# MegaShield.net
KiCad netlist of a schematic drawn in EAGLE
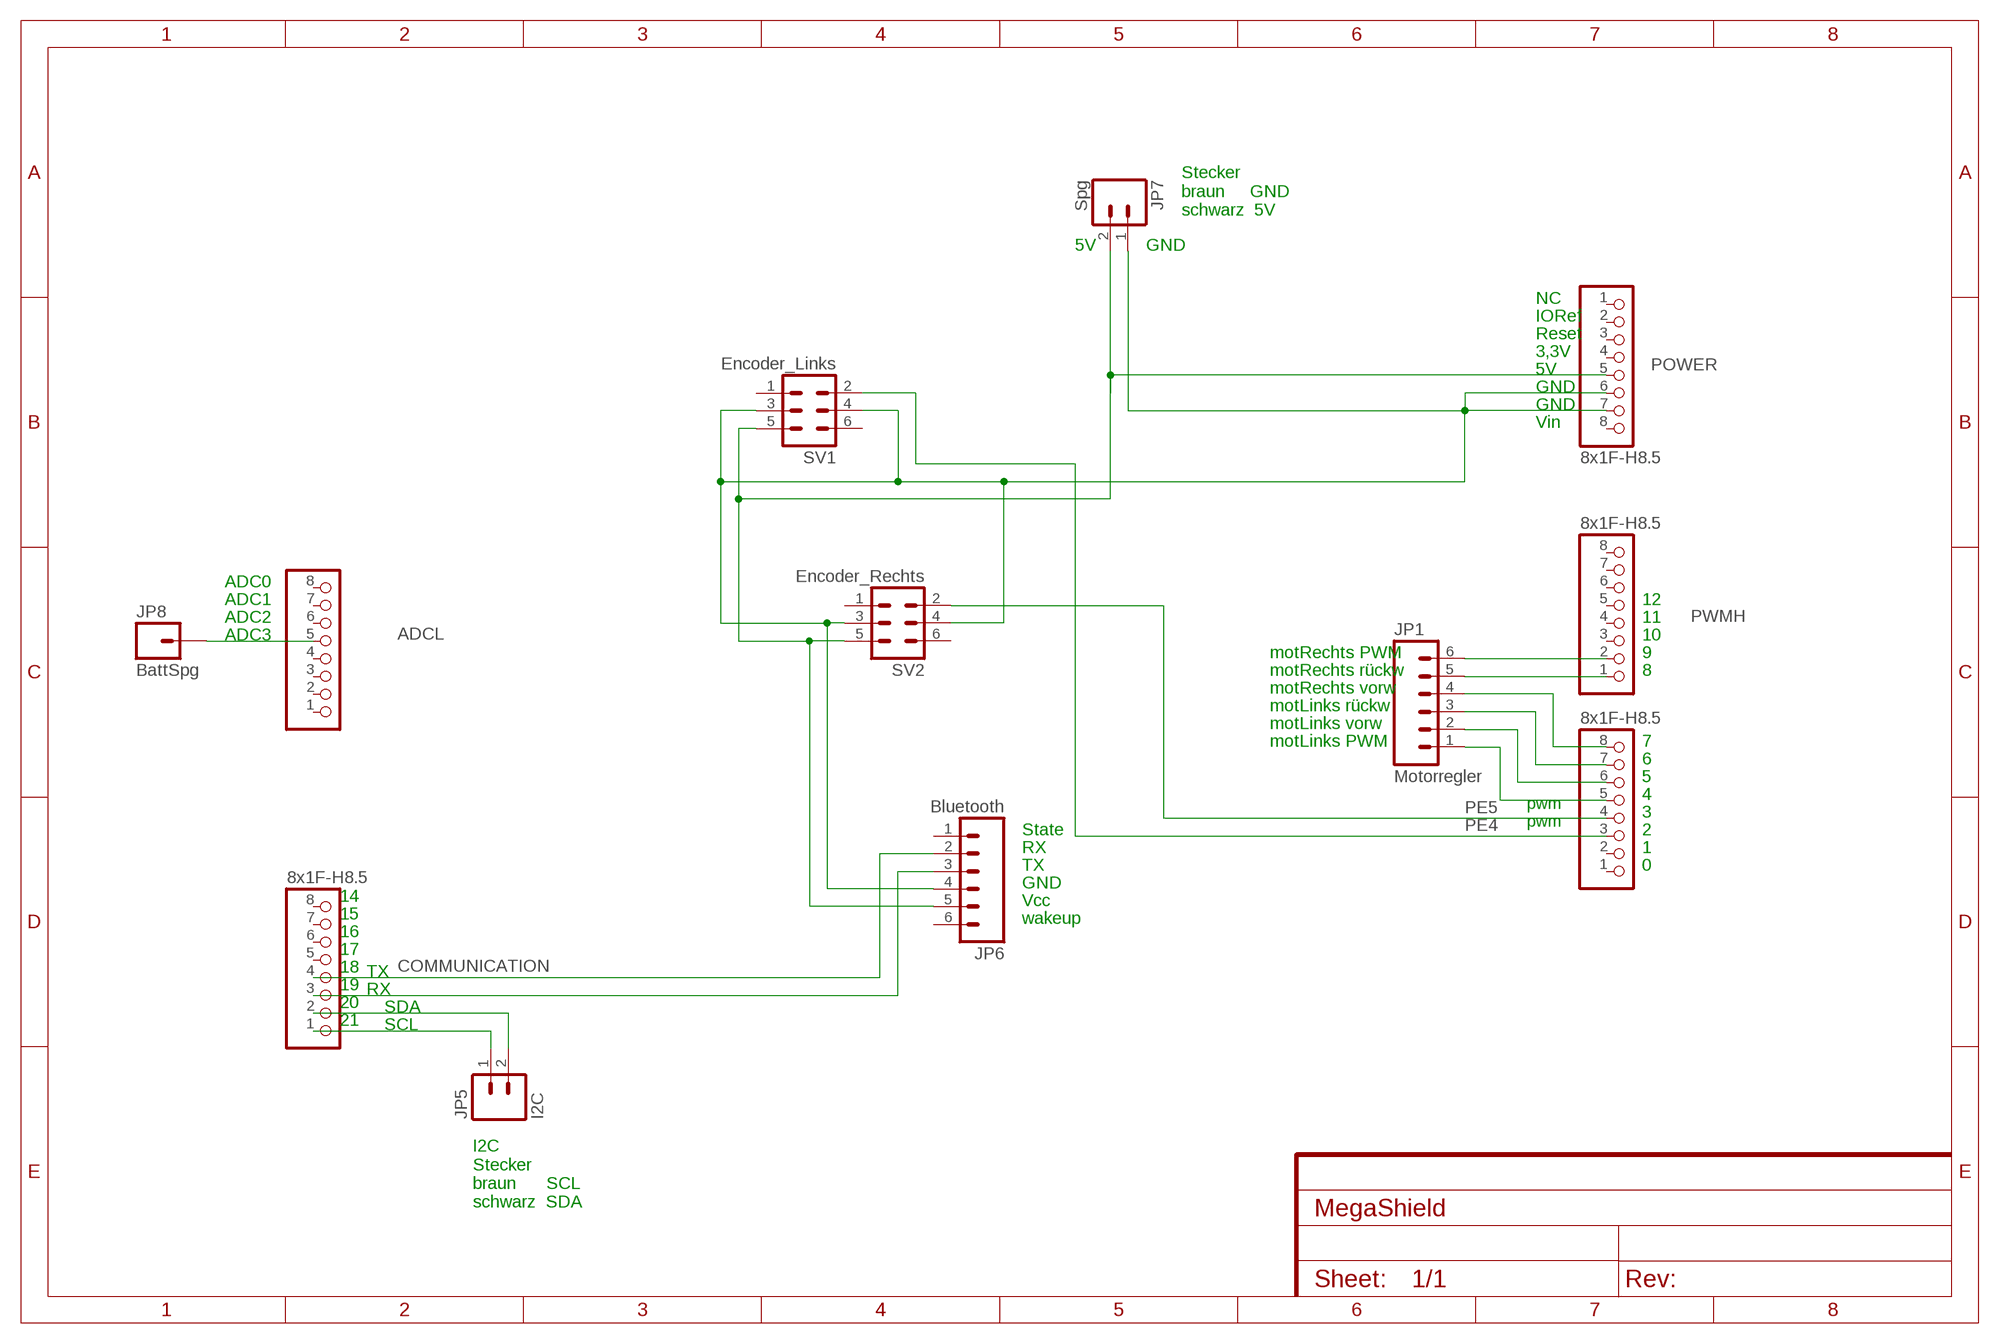
[diagram p0: schematic, sheet 1]

(export (version "E")
  (design (tool "Eeschema 10.0.6"))
  (components
    (comp (ref "ADCL")
      (value "8x1F-H8.5")
      (footprint "eagle-import:1X08")
      (libsource (lib "eagle-import") (part "PINHD-1X8"))
    )
    (comp (ref "COMMUNICATION")
      (value "8x1F-H8.5")
      (footprint "eagle-import:1X08")
      (libsource (lib "eagle-import") (part "PINHD-1X8"))
    )
    (comp (ref "JP1")
      (value "Motorregler")
      (footprint "eagle-import:1X06_LOCK")
      (libsource (lib "eagle-import") (part "M06LOCK"))
    )
    (comp (ref "JP5")
      (value "I2C")
      (footprint "eagle-import:JST-2-SMD")
      (libsource (lib "eagle-import") (part "M02-JST-2MM-SMT"))
    )
    (comp (ref "JP6")
      (value "Bluetooth")
      (footprint "eagle-import:1X06_LOCK")
      (libsource (lib "eagle-import") (part "M06LOCK"))
    )
    (comp (ref "JP7")
      (value "Spg")
      (footprint "eagle-import:JST-2-SMD")
      (libsource (lib "eagle-import") (part "M02-JST-2MM-SMT"))
    )
    (comp (ref "JP8")
      (value "BattSpg")
      (footprint "eagle-import:1X01")
      (libsource (lib "eagle-import") (part "M01PTH"))
    )
    (comp (ref "POWER")
      (value "8x1F-H8.5")
      (footprint "eagle-import:1X08")
      (libsource (lib "eagle-import") (part "PINHD-1X8"))
    )
    (comp (ref "PWMH")
      (value "8x1F-H8.5")
      (footprint "eagle-import:1X08")
      (libsource (lib "eagle-import") (part "PINHD-1X8"))
    )
    (comp (ref "PWML")
      (value "8x1F-H8.5")
      (footprint "eagle-import:1X08")
      (libsource (lib "eagle-import") (part "PINHD-1X8"))
    )
    (comp (ref "SV1")
      (value "Encoder_Links")
      (footprint "eagle-import:ML6")
      (libsource (lib "eagle-import") (part "ML6"))
    )
    (comp (ref "SV2")
      (value "Encoder_Rechts")
      (footprint "eagle-import:ML6")
      (libsource (lib "eagle-import") (part "ML6"))
    )
  )
  (nets
    (net (code "1") (name "/PE4") (class "Default")
      (node (ref "PWML") (pin "3") (pinfunction "3_3") (pintype "passive"))
      (node (ref "SV1") (pin "2") (pinfunction "2_2") (pintype "passive"))
    )
    (net (code "2") (name "/PE5") (class "Default")
      (node (ref "PWML") (pin "4") (pinfunction "4_4") (pintype "passive"))
      (node (ref "SV2") (pin "2") (pinfunction "2_2") (pintype "passive"))
    )
    (net (code "3") (name "Net-(ADCL-Pad5)") (class "Default")
      (node (ref "ADCL") (pin "5") (pinfunction "5_5") (pintype "passive"))
      (node (ref "JP8") (pin "1") (pinfunction "1_1") (pintype "passive"))
    )
    (net (code "4") (name "Net-(COMMUNICATION-Pad3)") (class "Default")
      (node (ref "COMMUNICATION") (pin "3") (pinfunction "3_3") (pintype "passive"))
      (node (ref "JP6") (pin "3") (pinfunction "3_3") (pintype "passive"))
    )
    (net (code "5") (name "Net-(COMMUNICATION-Pad4)") (class "Default")
      (node (ref "COMMUNICATION") (pin "4") (pinfunction "4_4") (pintype "passive"))
      (node (ref "JP6") (pin "2") (pinfunction "2_2") (pintype "passive"))
    )
    (net (code "6") (name "Net-(JP1-Pad1)") (class "Default")
      (node (ref "JP1") (pin "1") (pinfunction "1_1") (pintype "passive"))
      (node (ref "PWML") (pin "5") (pinfunction "5_5") (pintype "passive"))
    )
    (net (code "7") (name "Net-(JP1-Pad2)") (class "Default")
      (node (ref "JP1") (pin "2") (pinfunction "2_2") (pintype "passive"))
      (node (ref "PWML") (pin "6") (pinfunction "6_6") (pintype "passive"))
    )
    (net (code "8") (name "Net-(JP1-Pad3)") (class "Default")
      (node (ref "JP1") (pin "3") (pinfunction "3_3") (pintype "passive"))
      (node (ref "PWML") (pin "7") (pinfunction "7_7") (pintype "passive"))
    )
    (net (code "9") (name "Net-(JP1-Pad4)") (class "Default")
      (node (ref "JP1") (pin "4") (pinfunction "4_4") (pintype "passive"))
      (node (ref "PWML") (pin "8") (pinfunction "8_8") (pintype "passive"))
    )
    (net (code "10") (name "Net-(JP1-Pad5)") (class "Default")
      (node (ref "JP1") (pin "5") (pinfunction "5_5") (pintype "passive"))
      (node (ref "PWMH") (pin "1") (pinfunction "1_1") (pintype "passive"))
    )
    (net (code "11") (name "Net-(JP1-Pad6)") (class "Default")
      (node (ref "JP1") (pin "6") (pinfunction "6_6") (pintype "passive"))
      (node (ref "PWMH") (pin "2") (pinfunction "2_2") (pintype "passive"))
    )
    (net (code "12") (name "Net-(JP5-1)") (class "Default")
      (node (ref "COMMUNICATION") (pin "2") (pinfunction "2_2") (pintype "passive"))
      (node (ref "JP5") (pin "2") (pinfunction "1_2") (pintype "passive"))
    )
    (net (code "13") (name "Net-(JP5-2)") (class "Default")
      (node (ref "COMMUNICATION") (pin "1") (pinfunction "1_1") (pintype "passive"))
      (node (ref "JP5") (pin "1") (pinfunction "2_1") (pintype "passive"))
    )
    (net (code "14") (name "Net-(JP7-1)") (class "Default")
      (node (ref "JP6") (pin "5") (pinfunction "5_5") (pintype "passive"))
      (node (ref "JP7") (pin "2") (pinfunction "1_2") (pintype "passive"))
      (node (ref "POWER") (pin "5") (pinfunction "5_5") (pintype "passive"))
      (node (ref "SV1") (pin "5") (pinfunction "5_5") (pintype "passive"))
      (node (ref "SV2") (pin "5") (pinfunction "5_5") (pintype "passive"))
    )
    (net (code "15") (name "Net-(JP7-2)") (class "Default")
      (node (ref "JP6") (pin "4") (pinfunction "4_4") (pintype "passive"))
      (node (ref "JP7") (pin "1") (pinfunction "2_1") (pintype "passive"))
      (node (ref "POWER") (pin "6") (pinfunction "6_6") (pintype "passive"))
      (node (ref "POWER") (pin "7") (pinfunction "7_7") (pintype "passive"))
      (node (ref "SV1") (pin "3") (pinfunction "3_3") (pintype "passive"))
      (node (ref "SV1") (pin "4") (pinfunction "4_4") (pintype "passive"))
      (node (ref "SV2") (pin "3") (pinfunction "3_3") (pintype "passive"))
      (node (ref "SV2") (pin "4") (pinfunction "4_4") (pintype "passive"))
    )
    (net (code "16") (name "unconnected-(ADCL-Pad1)") (class "Default")
      (node (ref "ADCL") (pin "1") (pinfunction "1_1") (pintype "passive"))
    )
    (net (code "17") (name "unconnected-(ADCL-Pad2)") (class "Default")
      (node (ref "ADCL") (pin "2") (pinfunction "2_2") (pintype "passive"))
    )
    (net (code "18") (name "unconnected-(ADCL-Pad3)") (class "Default")
      (node (ref "ADCL") (pin "3") (pinfunction "3_3") (pintype "passive"))
    )
    (net (code "19") (name "unconnected-(ADCL-Pad4)") (class "Default")
      (node (ref "ADCL") (pin "4") (pinfunction "4_4") (pintype "passive"))
    )
    (net (code "20") (name "unconnected-(ADCL-Pad6)") (class "Default")
      (node (ref "ADCL") (pin "6") (pinfunction "6_6") (pintype "passive"))
    )
    (net (code "21") (name "unconnected-(ADCL-Pad7)") (class "Default")
      (node (ref "ADCL") (pin "7") (pinfunction "7_7") (pintype "passive"))
    )
    (net (code "22") (name "unconnected-(ADCL-Pad8)") (class "Default")
      (node (ref "ADCL") (pin "8") (pinfunction "8_8") (pintype "passive"))
    )
    (net (code "23") (name "unconnected-(COMMUNICATION-Pad5)") (class "Default")
      (node (ref "COMMUNICATION") (pin "5") (pinfunction "5_5") (pintype "passive"))
    )
    (net (code "24") (name "unconnected-(COMMUNICATION-Pad6)") (class "Default")
      (node (ref "COMMUNICATION") (pin "6") (pinfunction "6_6") (pintype "passive"))
    )
    (net (code "25") (name "unconnected-(COMMUNICATION-Pad7)") (class "Default")
      (node (ref "COMMUNICATION") (pin "7") (pinfunction "7_7") (pintype "passive"))
    )
    (net (code "26") (name "unconnected-(COMMUNICATION-Pad8)") (class "Default")
      (node (ref "COMMUNICATION") (pin "8") (pinfunction "8_8") (pintype "passive"))
    )
    (net (code "27") (name "unconnected-(JP6-Pad1)") (class "Default")
      (node (ref "JP6") (pin "1") (pinfunction "1_1") (pintype "passive"))
    )
    (net (code "28") (name "unconnected-(JP6-Pad6)") (class "Default")
      (node (ref "JP6") (pin "6") (pinfunction "6_6") (pintype "passive"))
    )
    (net (code "29") (name "unconnected-(POWER-Pad1)") (class "Default")
      (node (ref "POWER") (pin "1") (pinfunction "1_1") (pintype "passive"))
    )
    (net (code "30") (name "unconnected-(POWER-Pad2)") (class "Default")
      (node (ref "POWER") (pin "2") (pinfunction "2_2") (pintype "passive"))
    )
    (net (code "31") (name "unconnected-(POWER-Pad3)") (class "Default")
      (node (ref "POWER") (pin "3") (pinfunction "3_3") (pintype "passive"))
    )
    (net (code "32") (name "unconnected-(POWER-Pad4)") (class "Default")
      (node (ref "POWER") (pin "4") (pinfunction "4_4") (pintype "passive"))
    )
    (net (code "33") (name "unconnected-(POWER-Pad8)") (class "Default")
      (node (ref "POWER") (pin "8") (pinfunction "8_8") (pintype "passive"))
    )
    (net (code "34") (name "unconnected-(PWMH-Pad3)") (class "Default")
      (node (ref "PWMH") (pin "3") (pinfunction "3_3") (pintype "passive"))
    )
    (net (code "35") (name "unconnected-(PWMH-Pad4)") (class "Default")
      (node (ref "PWMH") (pin "4") (pinfunction "4_4") (pintype "passive"))
    )
    (net (code "36") (name "unconnected-(PWMH-Pad5)") (class "Default")
      (node (ref "PWMH") (pin "5") (pinfunction "5_5") (pintype "passive"))
    )
    (net (code "37") (name "unconnected-(PWMH-Pad6)") (class "Default")
      (node (ref "PWMH") (pin "6") (pinfunction "6_6") (pintype "passive"))
    )
    (net (code "38") (name "unconnected-(PWMH-Pad7)") (class "Default")
      (node (ref "PWMH") (pin "7") (pinfunction "7_7") (pintype "passive"))
    )
    (net (code "39") (name "unconnected-(PWMH-Pad8)") (class "Default")
      (node (ref "PWMH") (pin "8") (pinfunction "8_8") (pintype "passive"))
    )
    (net (code "40") (name "unconnected-(PWML-Pad1)") (class "Default")
      (node (ref "PWML") (pin "1") (pinfunction "1_1") (pintype "passive"))
    )
    (net (code "41") (name "unconnected-(PWML-Pad2)") (class "Default")
      (node (ref "PWML") (pin "2") (pinfunction "2_2") (pintype "passive"))
    )
    (net (code "42") (name "unconnected-(SV1-Pad1)") (class "Default")
      (node (ref "SV1") (pin "1") (pinfunction "1_1") (pintype "passive"))
    )
    (net (code "43") (name "unconnected-(SV1-Pad6)") (class "Default")
      (node (ref "SV1") (pin "6") (pinfunction "6_6") (pintype "passive"))
    )
    (net (code "44") (name "unconnected-(SV2-Pad1)") (class "Default")
      (node (ref "SV2") (pin "1") (pinfunction "1_1") (pintype "passive"))
    )
    (net (code "45") (name "unconnected-(SV2-Pad6)") (class "Default")
      (node (ref "SV2") (pin "6") (pinfunction "6_6") (pintype "passive"))
    )
  )
)
